# EMP5.net
KiCad netlist of a schematic drawn in EAGLE
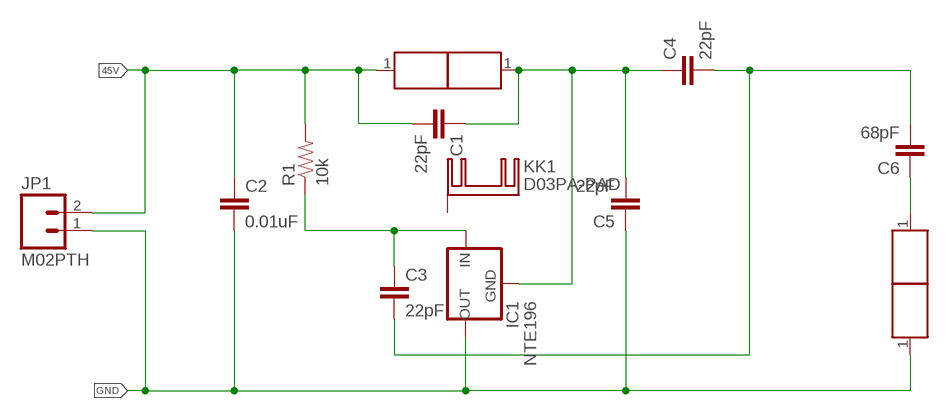
[diagram p0: schematic, sheet 1]

(export (version "E")
  (design (tool "Eeschema 10.0.6"))
  (components
    (comp (ref "C1")
      (value "22pF")
      (footprint "eagle-import:CAP-PTH-SMALL-KIT")
      (libsource (lib "eagle-import") (part "CAPKIT"))
    )
    (comp (ref "C2")
      (value "0.01uF")
      (footprint "eagle-import:CAP-PTH-SMALL-KIT")
      (libsource (lib "eagle-import") (part "CAPKIT"))
    )
    (comp (ref "C3")
      (value "22pF")
      (footprint "eagle-import:CAP-PTH-SMALL-KIT")
      (libsource (lib "eagle-import") (part "CAPKIT"))
    )
    (comp (ref "C4")
      (value "22pF")
      (footprint "eagle-import:CAP-PTH-SMALL-KIT")
      (libsource (lib "eagle-import") (part "CAPKIT"))
    )
    (comp (ref "C5")
      (value "22pF")
      (footprint "eagle-import:CAP-PTH-SMALL-KIT")
      (libsource (lib "eagle-import") (part "CAPKIT"))
    )
    (comp (ref "C6")
      (value "68pF")
      (footprint "eagle-import:CAP-PTH-SMALL-KIT")
      (libsource (lib "eagle-import") (part "CAPKIT"))
    )
    (comp (ref "IC1")
      (value "NTE196")
      (footprint "eagle-import:TO220-IGO")
      (libsource (lib "eagle-import") (part "V_REG_78XXSINK"))
    )
    (comp (ref "JP1")
      (value "M02PTH")
      (footprint "eagle-import:1X02")
      (libsource (lib "eagle-import") (part "M02PTH"))
    )
    (comp (ref "KK1")
      (value "D03PA-PAD")
      (footprint "eagle-import:D03PA-PAD")
      (libsource (lib "eagle-import") (part "D03PA-PAD"))
    )
    (comp (ref "L1-1")
      (value "L2_JOB37")
      (footprint "eagle-import:L2_JOB37")
      (libsource (lib "eagle-import") (part "L2_JOB37"))
    )
    (comp (ref "L1-2")
      (value "L2_JOB37")
      (footprint "eagle-import:L2_JOB37")
      (libsource (lib "eagle-import") (part "L2_JOB37"))
    )
    (comp (ref "L2-1")
      (value "L2_JOB37")
      (footprint "eagle-import:L2_JOB37")
      (libsource (lib "eagle-import") (part "L2_JOB37"))
    )
    (comp (ref "L2-2")
      (value "L2_JOB37")
      (footprint "eagle-import:L2_JOB37")
      (libsource (lib "eagle-import") (part "L2_JOB37"))
    )
    (comp (ref "R1")
      (value "10k")
      (footprint "eagle-import:AXIAL-0.3EZ")
      (libsource (lib "eagle-import") (part "RESISTOREZ"))
    )
  )
  (nets
    (net (code "1") (name "45V") (class "Default")
      (node (ref "C1") (pin "2") (pinfunction "2_2") (pintype "passive"))
      (node (ref "C2") (pin "1") (pinfunction "1_1") (pintype "passive"))
      (node (ref "JP1") (pin "2") (pinfunction "2_2") (pintype "passive"))
      (node (ref "L1-1") (pin "1") (pinfunction "1_1") (pintype "bidirectional"))
      (node (ref "R1") (pin "P$2") (pinfunction "2_P$2") (pintype "passive"))
    )
    (net (code "2") (name "GND") (class "Default")
      (node (ref "C2") (pin "2") (pinfunction "2_2") (pintype "passive"))
      (node (ref "C5") (pin "1") (pinfunction "1_1") (pintype "passive"))
      (node (ref "IC1") (pin "OUT") (pinfunction "OUT_OUT") (pintype "output"))
      (node (ref "JP1") (pin "1") (pinfunction "1_1") (pintype "passive"))
      (node (ref "L2-2") (pin "1") (pinfunction "1_1") (pintype "bidirectional"))
    )
    (net (code "3") (name "Net-(C1-Pad1)") (class "Default")
      (node (ref "C1") (pin "1") (pinfunction "1_1") (pintype "passive"))
      (node (ref "C4") (pin "1") (pinfunction "1_1") (pintype "passive"))
      (node (ref "C5") (pin "2") (pinfunction "2_2") (pintype "passive"))
      (node (ref "IC1") (pin "GND") (pinfunction "GND_GND") (pintype "input"))
      (node (ref "L1-2") (pin "1") (pinfunction "1_1") (pintype "bidirectional"))
    )
    (net (code "4") (name "Net-(C3-Pad2)") (class "Default")
      (node (ref "C3") (pin "2") (pinfunction "2_2") (pintype "passive"))
      (node (ref "C4") (pin "2") (pinfunction "2_2") (pintype "passive"))
      (node (ref "C6") (pin "2") (pinfunction "2_2") (pintype "passive"))
    )
    (net (code "5") (name "Net-(C6-Pad1)") (class "Default")
      (node (ref "C6") (pin "1") (pinfunction "1_1") (pintype "passive"))
      (node (ref "L2-1") (pin "1") (pinfunction "1_1") (pintype "bidirectional"))
    )
    (net (code "6") (name "Net-(R1-1)") (class "Default")
      (node (ref "C3") (pin "1") (pinfunction "1_1") (pintype "passive"))
      (node (ref "IC1") (pin "IN") (pinfunction "IN_IN") (pintype "input"))
      (node (ref "R1") (pin "P$1") (pinfunction "1_P$1") (pintype "passive"))
    )
    (net (code "7") (name "unconnected-(KK1-K-PadB)") (class "Default")
      (node (ref "KK1") (pin "B") (pinfunction "K_B") (pintype "passive"))
    )
  )
)
